# esquematico_tsal_mainhoop.net
KiCad netlist of a schematic drawn in Altium Designer
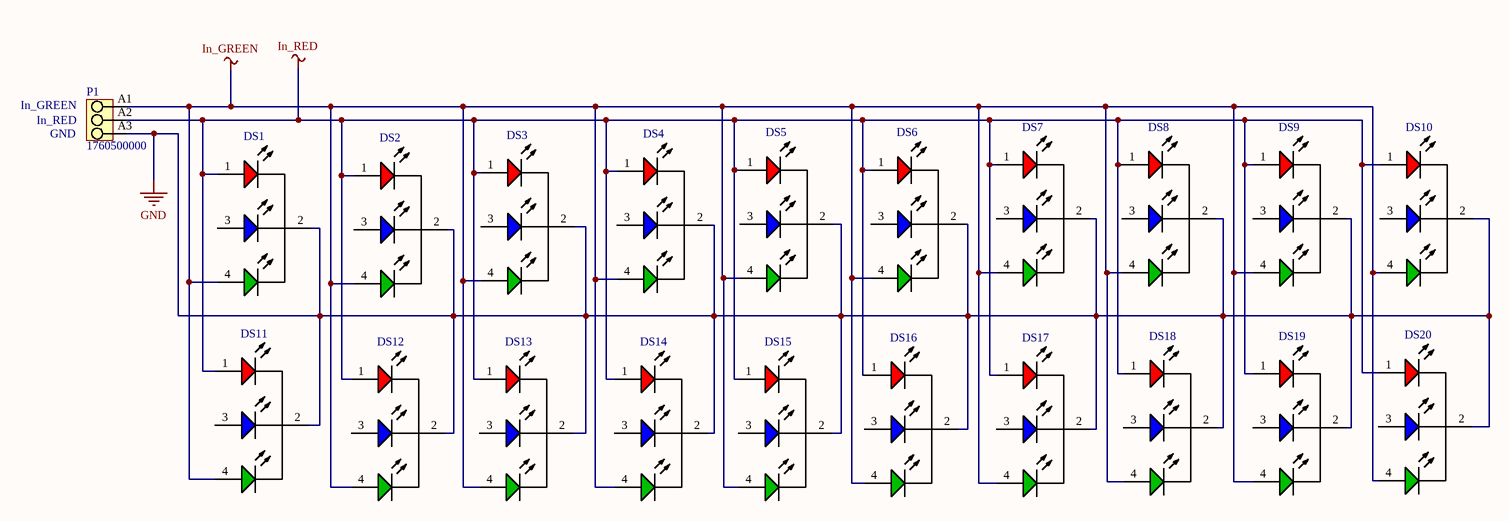
[diagram p0: esquematico_tsal_mainhoop.SchDoc]

(export (version "E")
  (design (tool "Eeschema 10.0.6"))
  (components
    (comp (ref "DS1")
      (value "WP154A4SUREQBFZGC")
      (footprint "KING-WP154A4SUREQBFZGC_V")
      (description "Full Color LED Lamp, Dominant Wavelength RGB 630 / 525 / 465 nm, -40 to 85 degC, 4-Pin THD, RoHS")
      (fields (field (name "MANUFACTURER") "Kingbright"))
      (libsource (lib "Altium Content Vault") (part "LED-RGB-AKAA-4"))
    )
    (comp (ref "DS2")
      (value "WP154A4SUREQBFZGC")
      (footprint "KING-WP154A4SUREQBFZGC_V")
      (description "Full Color LED Lamp, Dominant Wavelength RGB 630 / 525 / 465 nm, -40 to 85 degC, 4-Pin THD, RoHS")
      (fields (field (name "MANUFACTURER") "Kingbright"))
      (libsource (lib "Altium Content Vault") (part "LED-RGB-AKAA-4"))
    )
    (comp (ref "DS3")
      (value "WP154A4SUREQBFZGC")
      (footprint "KING-WP154A4SUREQBFZGC_V")
      (description "Full Color LED Lamp, Dominant Wavelength RGB 630 / 525 / 465 nm, -40 to 85 degC, 4-Pin THD, RoHS")
      (fields (field (name "MANUFACTURER") "Kingbright"))
      (libsource (lib "Altium Content Vault") (part "LED-RGB-AKAA-4"))
    )
    (comp (ref "DS4")
      (value "WP154A4SUREQBFZGC")
      (footprint "KING-WP154A4SUREQBFZGC_V")
      (description "Full Color LED Lamp, Dominant Wavelength RGB 630 / 525 / 465 nm, -40 to 85 degC, 4-Pin THD, RoHS")
      (fields (field (name "MANUFACTURER") "Kingbright"))
      (libsource (lib "Altium Content Vault") (part "LED-RGB-AKAA-4"))
    )
    (comp (ref "DS5")
      (value "WP154A4SUREQBFZGC")
      (footprint "KING-WP154A4SUREQBFZGC_V")
      (description "Full Color LED Lamp, Dominant Wavelength RGB 630 / 525 / 465 nm, -40 to 85 degC, 4-Pin THD, RoHS")
      (fields (field (name "MANUFACTURER") "Kingbright"))
      (libsource (lib "Altium Content Vault") (part "LED-RGB-AKAA-4"))
    )
    (comp (ref "DS6")
      (value "WP154A4SUREQBFZGC")
      (footprint "KING-WP154A4SUREQBFZGC_V")
      (description "Full Color LED Lamp, Dominant Wavelength RGB 630 / 525 / 465 nm, -40 to 85 degC, 4-Pin THD, RoHS")
      (fields (field (name "MANUFACTURER") "Kingbright"))
      (libsource (lib "Altium Content Vault") (part "LED-RGB-AKAA-4"))
    )
    (comp (ref "DS7")
      (value "WP154A4SUREQBFZGC")
      (footprint "KING-WP154A4SUREQBFZGC_V")
      (description "Full Color LED Lamp, Dominant Wavelength RGB 630 / 525 / 465 nm, -40 to 85 degC, 4-Pin THD, RoHS")
      (fields (field (name "MANUFACTURER") "Kingbright"))
      (libsource (lib "Altium Content Vault") (part "LED-RGB-AKAA-4"))
    )
    (comp (ref "DS8")
      (value "WP154A4SUREQBFZGC")
      (footprint "KING-WP154A4SUREQBFZGC_V")
      (description "Full Color LED Lamp, Dominant Wavelength RGB 630 / 525 / 465 nm, -40 to 85 degC, 4-Pin THD, RoHS")
      (fields (field (name "MANUFACTURER") "Kingbright"))
      (libsource (lib "Altium Content Vault") (part "LED-RGB-AKAA-4"))
    )
    (comp (ref "DS9")
      (value "WP154A4SUREQBFZGC")
      (footprint "KING-WP154A4SUREQBFZGC_V")
      (description "Full Color LED Lamp, Dominant Wavelength RGB 630 / 525 / 465 nm, -40 to 85 degC, 4-Pin THD, RoHS")
      (fields (field (name "MANUFACTURER") "Kingbright"))
      (libsource (lib "Altium Content Vault") (part "LED-RGB-AKAA-4"))
    )
    (comp (ref "DS10")
      (value "WP154A4SUREQBFZGC")
      (footprint "KING-WP154A4SUREQBFZGC_V")
      (description "Full Color LED Lamp, Dominant Wavelength RGB 630 / 525 / 465 nm, -40 to 85 degC, 4-Pin THD, RoHS")
      (fields (field (name "MANUFACTURER") "Kingbright"))
      (libsource (lib "Altium Content Vault") (part "LED-RGB-AKAA-4"))
    )
    (comp (ref "DS11")
      (value "WP154A4SUREQBFZGC")
      (footprint "KING-WP154A4SUREQBFZGC_V")
      (description "Full Color LED Lamp, Dominant Wavelength RGB 630 / 525 / 465 nm, -40 to 85 degC, 4-Pin THD, RoHS")
      (fields (field (name "MANUFACTURER") "Kingbright"))
      (libsource (lib "Altium Content Vault") (part "LED-RGB-AKAA-4"))
    )
    (comp (ref "DS12")
      (value "WP154A4SUREQBFZGC")
      (footprint "KING-WP154A4SUREQBFZGC_V")
      (description "Full Color LED Lamp, Dominant Wavelength RGB 630 / 525 / 465 nm, -40 to 85 degC, 4-Pin THD, RoHS")
      (fields (field (name "MANUFACTURER") "Kingbright"))
      (libsource (lib "Altium Content Vault") (part "LED-RGB-AKAA-4"))
    )
    (comp (ref "DS13")
      (value "WP154A4SUREQBFZGC")
      (footprint "KING-WP154A4SUREQBFZGC_V")
      (description "Full Color LED Lamp, Dominant Wavelength RGB 630 / 525 / 465 nm, -40 to 85 degC, 4-Pin THD, RoHS")
      (fields (field (name "MANUFACTURER") "Kingbright"))
      (libsource (lib "Altium Content Vault") (part "LED-RGB-AKAA-4"))
    )
    (comp (ref "DS14")
      (value "WP154A4SUREQBFZGC")
      (footprint "KING-WP154A4SUREQBFZGC_V")
      (description "Full Color LED Lamp, Dominant Wavelength RGB 630 / 525 / 465 nm, -40 to 85 degC, 4-Pin THD, RoHS")
      (fields (field (name "MANUFACTURER") "Kingbright"))
      (libsource (lib "Altium Content Vault") (part "LED-RGB-AKAA-4"))
    )
    (comp (ref "DS15")
      (value "WP154A4SUREQBFZGC")
      (footprint "KING-WP154A4SUREQBFZGC_V")
      (description "Full Color LED Lamp, Dominant Wavelength RGB 630 / 525 / 465 nm, -40 to 85 degC, 4-Pin THD, RoHS")
      (fields (field (name "MANUFACTURER") "Kingbright"))
      (libsource (lib "Altium Content Vault") (part "LED-RGB-AKAA-4"))
    )
    (comp (ref "DS16")
      (value "WP154A4SUREQBFZGC")
      (footprint "KING-WP154A4SUREQBFZGC_V")
      (description "Full Color LED Lamp, Dominant Wavelength RGB 630 / 525 / 465 nm, -40 to 85 degC, 4-Pin THD, RoHS")
      (fields (field (name "MANUFACTURER") "Kingbright"))
      (libsource (lib "Altium Content Vault") (part "LED-RGB-AKAA-4"))
    )
    (comp (ref "DS17")
      (value "WP154A4SUREQBFZGC")
      (footprint "KING-WP154A4SUREQBFZGC_V")
      (description "Full Color LED Lamp, Dominant Wavelength RGB 630 / 525 / 465 nm, -40 to 85 degC, 4-Pin THD, RoHS")
      (fields (field (name "MANUFACTURER") "Kingbright"))
      (libsource (lib "Altium Content Vault") (part "LED-RGB-AKAA-4"))
    )
    (comp (ref "DS18")
      (value "WP154A4SUREQBFZGC")
      (footprint "KING-WP154A4SUREQBFZGC_V")
      (description "Full Color LED Lamp, Dominant Wavelength RGB 630 / 525 / 465 nm, -40 to 85 degC, 4-Pin THD, RoHS")
      (fields (field (name "MANUFACTURER") "Kingbright"))
      (libsource (lib "Altium Content Vault") (part "LED-RGB-AKAA-4"))
    )
    (comp (ref "DS19")
      (value "WP154A4SUREQBFZGC")
      (footprint "KING-WP154A4SUREQBFZGC_V")
      (description "Full Color LED Lamp, Dominant Wavelength RGB 630 / 525 / 465 nm, -40 to 85 degC, 4-Pin THD, RoHS")
      (fields (field (name "MANUFACTURER") "Kingbright"))
      (libsource (lib "Altium Content Vault") (part "LED-RGB-AKAA-4"))
    )
    (comp (ref "DS20")
      (value "WP154A4SUREQBFZGC")
      (footprint "KING-WP154A4SUREQBFZGC_V")
      (description "Full Color LED Lamp, Dominant Wavelength RGB 630 / 525 / 465 nm, -40 to 85 degC, 4-Pin THD, RoHS")
      (fields (field (name "MANUFACTURER") "Kingbright"))
      (libsource (lib "Altium Content Vault") (part "LED-RGB-AKAA-4"))
    )
    (comp (ref "P1")
      (value "1760500000")
      (footprint "PM_5_08_90_03")
      (description "OMNIMATE Signal - series PM")
      (fields (field (name "MANUFACTURER") "Weidmueller"))
      (libsource (lib "Altium Content Vault") (part "Terminal_03_1x03"))
    )
  )
  (nets
    (net (code "1") (name "GND") (class "Default")
      (node (ref "DS1") (pin "2") (pinfunction "CATHODE_2") (pintype "passive"))
      (node (ref "DS10") (pin "2") (pinfunction "CATHODE_2") (pintype "passive"))
      (node (ref "DS11") (pin "2") (pinfunction "CATHODE_2") (pintype "passive"))
      (node (ref "DS12") (pin "2") (pinfunction "CATHODE_2") (pintype "passive"))
      (node (ref "DS13") (pin "2") (pinfunction "CATHODE_2") (pintype "passive"))
      (node (ref "DS14") (pin "2") (pinfunction "CATHODE_2") (pintype "passive"))
      (node (ref "DS15") (pin "2") (pinfunction "CATHODE_2") (pintype "passive"))
      (node (ref "DS16") (pin "2") (pinfunction "CATHODE_2") (pintype "passive"))
      (node (ref "DS17") (pin "2") (pinfunction "CATHODE_2") (pintype "passive"))
      (node (ref "DS18") (pin "2") (pinfunction "CATHODE_2") (pintype "passive"))
      (node (ref "DS19") (pin "2") (pinfunction "CATHODE_2") (pintype "passive"))
      (node (ref "DS2") (pin "2") (pinfunction "CATHODE_2") (pintype "passive"))
      (node (ref "DS20") (pin "2") (pinfunction "CATHODE_2") (pintype "passive"))
      (node (ref "DS3") (pin "2") (pinfunction "CATHODE_2") (pintype "passive"))
      (node (ref "DS4") (pin "2") (pinfunction "CATHODE_2") (pintype "passive"))
      (node (ref "DS5") (pin "2") (pinfunction "CATHODE_2") (pintype "passive"))
      (node (ref "DS6") (pin "2") (pinfunction "CATHODE_2") (pintype "passive"))
      (node (ref "DS7") (pin "2") (pinfunction "CATHODE_2") (pintype "passive"))
      (node (ref "DS8") (pin "2") (pinfunction "CATHODE_2") (pintype "passive"))
      (node (ref "DS9") (pin "2") (pinfunction "CATHODE_2") (pintype "passive"))
      (node (ref "P1") (pin "A3") (pinfunction "A3_A3") (pintype "passive"))
    )
    (net (code "2") (name "In_GREEN") (class "Default")
      (node (ref "DS1") (pin "4") (pinfunction "GREEN_4") (pintype "passive"))
      (node (ref "DS10") (pin "4") (pinfunction "GREEN_4") (pintype "passive"))
      (node (ref "DS11") (pin "4") (pinfunction "GREEN_4") (pintype "passive"))
      (node (ref "DS12") (pin "4") (pinfunction "GREEN_4") (pintype "passive"))
      (node (ref "DS13") (pin "4") (pinfunction "GREEN_4") (pintype "passive"))
      (node (ref "DS14") (pin "4") (pinfunction "GREEN_4") (pintype "passive"))
      (node (ref "DS15") (pin "4") (pinfunction "GREEN_4") (pintype "passive"))
      (node (ref "DS16") (pin "4") (pinfunction "GREEN_4") (pintype "passive"))
      (node (ref "DS17") (pin "4") (pinfunction "GREEN_4") (pintype "passive"))
      (node (ref "DS18") (pin "4") (pinfunction "GREEN_4") (pintype "passive"))
      (node (ref "DS19") (pin "4") (pinfunction "GREEN_4") (pintype "passive"))
      (node (ref "DS2") (pin "4") (pinfunction "GREEN_4") (pintype "passive"))
      (node (ref "DS20") (pin "4") (pinfunction "GREEN_4") (pintype "passive"))
      (node (ref "DS3") (pin "4") (pinfunction "GREEN_4") (pintype "passive"))
      (node (ref "DS4") (pin "4") (pinfunction "GREEN_4") (pintype "passive"))
      (node (ref "DS5") (pin "4") (pinfunction "GREEN_4") (pintype "passive"))
      (node (ref "DS6") (pin "4") (pinfunction "GREEN_4") (pintype "passive"))
      (node (ref "DS7") (pin "4") (pinfunction "GREEN_4") (pintype "passive"))
      (node (ref "DS8") (pin "4") (pinfunction "GREEN_4") (pintype "passive"))
      (node (ref "DS9") (pin "4") (pinfunction "GREEN_4") (pintype "passive"))
      (node (ref "P1") (pin "A1") (pinfunction "A1_A1") (pintype "passive"))
    )
    (net (code "3") (name "In_RED") (class "Default")
      (node (ref "DS1") (pin "1") (pinfunction "RED_1") (pintype "passive"))
      (node (ref "DS10") (pin "1") (pinfunction "RED_1") (pintype "passive"))
      (node (ref "DS11") (pin "1") (pinfunction "RED_1") (pintype "passive"))
      (node (ref "DS12") (pin "1") (pinfunction "RED_1") (pintype "passive"))
      (node (ref "DS13") (pin "1") (pinfunction "RED_1") (pintype "passive"))
      (node (ref "DS14") (pin "1") (pinfunction "RED_1") (pintype "passive"))
      (node (ref "DS15") (pin "1") (pinfunction "RED_1") (pintype "passive"))
      (node (ref "DS16") (pin "1") (pinfunction "RED_1") (pintype "passive"))
      (node (ref "DS17") (pin "1") (pinfunction "RED_1") (pintype "passive"))
      (node (ref "DS18") (pin "1") (pinfunction "RED_1") (pintype "passive"))
      (node (ref "DS19") (pin "1") (pinfunction "RED_1") (pintype "passive"))
      (node (ref "DS2") (pin "1") (pinfunction "RED_1") (pintype "passive"))
      (node (ref "DS20") (pin "1") (pinfunction "RED_1") (pintype "passive"))
      (node (ref "DS3") (pin "1") (pinfunction "RED_1") (pintype "passive"))
      (node (ref "DS4") (pin "1") (pinfunction "RED_1") (pintype "passive"))
      (node (ref "DS5") (pin "1") (pinfunction "RED_1") (pintype "passive"))
      (node (ref "DS6") (pin "1") (pinfunction "RED_1") (pintype "passive"))
      (node (ref "DS7") (pin "1") (pinfunction "RED_1") (pintype "passive"))
      (node (ref "DS8") (pin "1") (pinfunction "RED_1") (pintype "passive"))
      (node (ref "DS9") (pin "1") (pinfunction "RED_1") (pintype "passive"))
      (node (ref "P1") (pin "A2") (pinfunction "A2_A2") (pintype "passive"))
    )
    (net (code "4") (name "unconnected-(DS1-BLUE-Pad3)") (class "Default")
      (node (ref "DS1") (pin "3") (pinfunction "BLUE_3") (pintype "passive"))
    )
    (net (code "5") (name "unconnected-(DS2-BLUE-Pad3)") (class "Default")
      (node (ref "DS2") (pin "3") (pinfunction "BLUE_3") (pintype "passive"))
    )
    (net (code "6") (name "unconnected-(DS3-BLUE-Pad3)") (class "Default")
      (node (ref "DS3") (pin "3") (pinfunction "BLUE_3") (pintype "passive"))
    )
    (net (code "7") (name "unconnected-(DS4-BLUE-Pad3)") (class "Default")
      (node (ref "DS4") (pin "3") (pinfunction "BLUE_3") (pintype "passive"))
    )
    (net (code "8") (name "unconnected-(DS5-BLUE-Pad3)") (class "Default")
      (node (ref "DS5") (pin "3") (pinfunction "BLUE_3") (pintype "passive"))
    )
    (net (code "9") (name "unconnected-(DS6-BLUE-Pad3)") (class "Default")
      (node (ref "DS6") (pin "3") (pinfunction "BLUE_3") (pintype "passive"))
    )
    (net (code "10") (name "unconnected-(DS7-BLUE-Pad3)") (class "Default")
      (node (ref "DS7") (pin "3") (pinfunction "BLUE_3") (pintype "passive"))
    )
    (net (code "11") (name "unconnected-(DS8-BLUE-Pad3)") (class "Default")
      (node (ref "DS8") (pin "3") (pinfunction "BLUE_3") (pintype "passive"))
    )
    (net (code "12") (name "unconnected-(DS9-BLUE-Pad3)") (class "Default")
      (node (ref "DS9") (pin "3") (pinfunction "BLUE_3") (pintype "passive"))
    )
    (net (code "13") (name "unconnected-(DS10-BLUE-Pad3)") (class "Default")
      (node (ref "DS10") (pin "3") (pinfunction "BLUE_3") (pintype "passive"))
    )
    (net (code "14") (name "unconnected-(DS11-BLUE-Pad3)") (class "Default")
      (node (ref "DS11") (pin "3") (pinfunction "BLUE_3") (pintype "passive"))
    )
    (net (code "15") (name "unconnected-(DS12-BLUE-Pad3)") (class "Default")
      (node (ref "DS12") (pin "3") (pinfunction "BLUE_3") (pintype "passive"))
    )
    (net (code "16") (name "unconnected-(DS13-BLUE-Pad3)") (class "Default")
      (node (ref "DS13") (pin "3") (pinfunction "BLUE_3") (pintype "passive"))
    )
    (net (code "17") (name "unconnected-(DS14-BLUE-Pad3)") (class "Default")
      (node (ref "DS14") (pin "3") (pinfunction "BLUE_3") (pintype "passive"))
    )
    (net (code "18") (name "unconnected-(DS15-BLUE-Pad3)") (class "Default")
      (node (ref "DS15") (pin "3") (pinfunction "BLUE_3") (pintype "passive"))
    )
    (net (code "19") (name "unconnected-(DS16-BLUE-Pad3)") (class "Default")
      (node (ref "DS16") (pin "3") (pinfunction "BLUE_3") (pintype "passive"))
    )
    (net (code "20") (name "unconnected-(DS17-BLUE-Pad3)") (class "Default")
      (node (ref "DS17") (pin "3") (pinfunction "BLUE_3") (pintype "passive"))
    )
    (net (code "21") (name "unconnected-(DS18-BLUE-Pad3)") (class "Default")
      (node (ref "DS18") (pin "3") (pinfunction "BLUE_3") (pintype "passive"))
    )
    (net (code "22") (name "unconnected-(DS19-BLUE-Pad3)") (class "Default")
      (node (ref "DS19") (pin "3") (pinfunction "BLUE_3") (pintype "passive"))
    )
    (net (code "23") (name "unconnected-(DS20-BLUE-Pad3)") (class "Default")
      (node (ref "DS20") (pin "3") (pinfunction "BLUE_3") (pintype "passive"))
    )
  )
)
